# MCU_V1.net
KiCad netlist of a schematic drawn in EAGLE
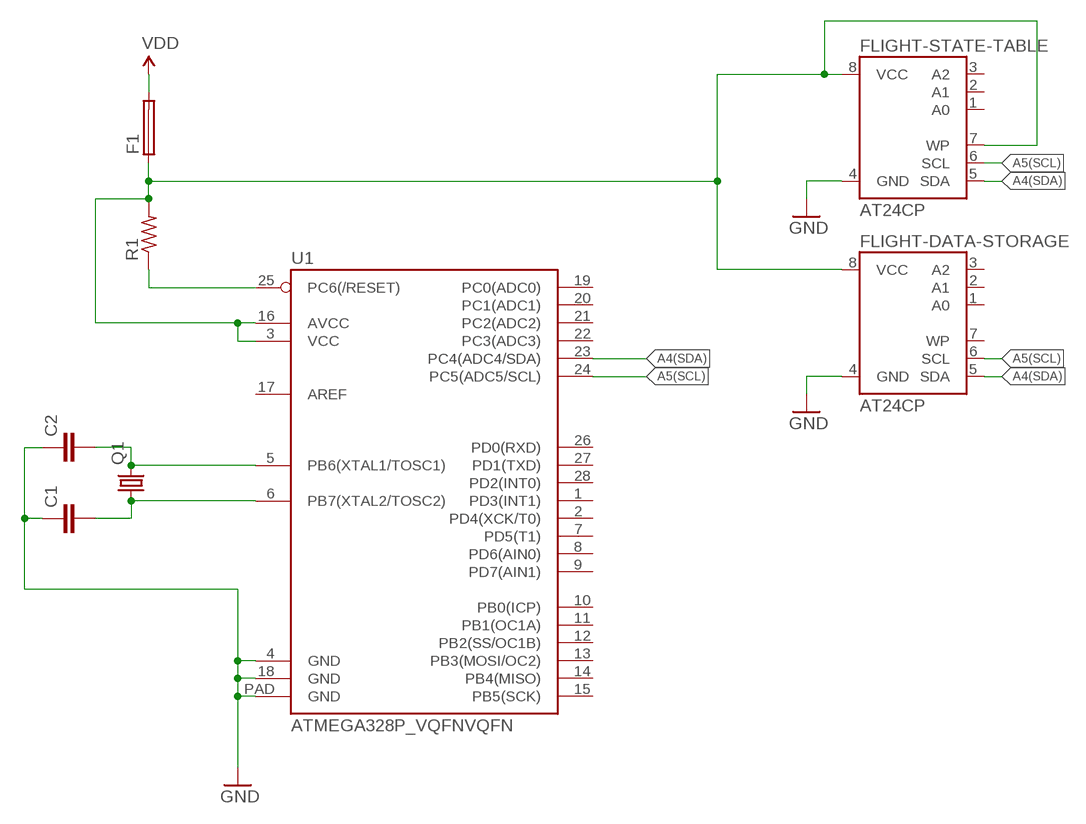
[diagram p0: schematic, sheet 1]

(export (version "E")
  (design (tool "Eeschema 10.0.6"))
  (components
    (comp (ref "C1")
      (value "C2,5-3")
      (footprint "eagle-import:C2.5-3")
      (libsource (lib "eagle-import") (part "C2,5-3"))
    )
    (comp (ref "C2")
      (value "C2,5-3")
      (footprint "eagle-import:C2.5-3")
      (libsource (lib "eagle-import") (part "C2,5-3"))
    )
    (comp (ref "F1")
      (value "19559")
      (footprint "eagle-import:19559")
      (fields (field (name "MPN") "55900000001"))
      (libsource (lib "eagle-import") (part "19559"))
    )
    (comp (ref "FLIGHT-DATA-STORAGE")
      (value "AT24CP")
      (footprint "eagle-import:DIL08")
      (fields (field (name "MPN") "AT24C1024BW-SH-B"))
      (libsource (lib "eagle-import") (part "AT24CP"))
    )
    (comp (ref "FLIGHT-STATE-TABLE")
      (value "AT24CP")
      (footprint "eagle-import:DIL08")
      (fields (field (name "MPN") "AT24C1024BW-SH-B"))
      (libsource (lib "eagle-import") (part "AT24CP"))
    )
    (comp (ref "Q1")
      (value "CRYSTALHC33U-V")
      (footprint "eagle-import:HC33U-V")
      (libsource (lib "eagle-import") (part "CRYSTALHC33U-V"))
    )
    (comp (ref "R1")
      (value "R-US_R0805")
      (footprint "eagle-import:R0805")
      (libsource (lib "eagle-import") (part "R-US_R0805"))
    )
    (comp (ref "U1")
      (value "ATMEGA328P_VQFNVQFN")
      (footprint "eagle-import:VQFN-28")
      (libsource (lib "eagle-import") (part "ATMEGA328P_VQFNVQFN"))
    )
  )
  (nets
    (net (code "1") (name "A4(SDA)") (class "Default")
      (node (ref "FLIGHT-DATA-STORAGE") (pin "5") (pinfunction "SDA_5") (pintype "bidirectional"))
      (node (ref "FLIGHT-STATE-TABLE") (pin "5") (pinfunction "SDA_5") (pintype "bidirectional"))
      (node (ref "U1") (pin "23") (pinfunction "PC4(ADC4/SDA)_23") (pintype "bidirectional"))
    )
    (net (code "2") (name "A5(SCL)") (class "Default")
      (node (ref "FLIGHT-DATA-STORAGE") (pin "6") (pinfunction "SCL_6") (pintype "bidirectional"))
      (node (ref "FLIGHT-STATE-TABLE") (pin "6") (pinfunction "SCL_6") (pintype "bidirectional"))
      (node (ref "U1") (pin "24") (pinfunction "PC5(ADC5/SCL)_24") (pintype "bidirectional"))
    )
    (net (code "3") (name "GND") (class "Default")
      (node (ref "C1") (pin "1") (pinfunction "1_1") (pintype "passive"))
      (node (ref "C2") (pin "1") (pinfunction "1_1") (pintype "passive"))
      (node (ref "FLIGHT-DATA-STORAGE") (pin "4") (pinfunction "GND_4") (pintype "power_in"))
      (node (ref "FLIGHT-STATE-TABLE") (pin "4") (pinfunction "GND_4") (pintype "power_in"))
      (node (ref "U1") (pin "18") (pinfunction "GND_18") (pintype "bidirectional"))
      (node (ref "U1") (pin "4") (pinfunction "GND_4") (pintype "bidirectional"))
      (node (ref "U1") (pin "PAD") (pinfunction "GND_PAD") (pintype "bidirectional"))
    )
    (net (code "4") (name "Net-(FLIGHT-DATA-STORAGE-VCC)") (class "Default")
      (node (ref "F1") (pin "1") (pinfunction "1_1") (pintype "passive"))
      (node (ref "FLIGHT-DATA-STORAGE") (pin "8") (pinfunction "VCC_8") (pintype "power_in"))
      (node (ref "FLIGHT-STATE-TABLE") (pin "7") (pinfunction "WP_7") (pintype "input"))
      (node (ref "FLIGHT-STATE-TABLE") (pin "8") (pinfunction "VCC_8") (pintype "power_in"))
      (node (ref "R1") (pin "2") (pinfunction "2_2") (pintype "passive"))
      (node (ref "U1") (pin "16") (pinfunction "AVCC_16") (pintype "bidirectional"))
      (node (ref "U1") (pin "3") (pinfunction "VCC_3") (pintype "bidirectional"))
    )
    (net (code "5") (name "Net-(U1-PB6(XTAL1{slash}TOSC1))") (class "Default")
      (node (ref "C2") (pin "2") (pinfunction "2_2") (pintype "passive"))
      (node (ref "Q1") (pin "2") (pinfunction "2_2") (pintype "passive"))
      (node (ref "U1") (pin "5") (pinfunction "PB6(XTAL1/TOSC1)_5") (pintype "bidirectional"))
    )
    (net (code "6") (name "Net-(U1-PB7(XTAL2{slash}TOSC2))") (class "Default")
      (node (ref "C1") (pin "2") (pinfunction "2_2") (pintype "passive"))
      (node (ref "Q1") (pin "1") (pinfunction "1_1") (pintype "passive"))
      (node (ref "U1") (pin "6") (pinfunction "PB7(XTAL2/TOSC2)_6") (pintype "bidirectional"))
    )
    (net (code "7") (name "Net-(U1-PC6({slash}RESET))") (class "Default")
      (node (ref "R1") (pin "1") (pinfunction "1_1") (pintype "passive"))
      (node (ref "U1") (pin "25") (pinfunction "PC6(/RESET)_25") (pintype "bidirectional"))
    )
    (net (code "8") (name "VDD") (class "Default")
      (node (ref "F1") (pin "2") (pinfunction "2_2") (pintype "passive"))
    )
    (net (code "9") (name "unconnected-(FLIGHT-DATA-STORAGE-A0-Pad1)") (class "Default")
      (node (ref "FLIGHT-DATA-STORAGE") (pin "1") (pinfunction "A0_1") (pintype "input"))
    )
    (net (code "10") (name "unconnected-(FLIGHT-DATA-STORAGE-A1-Pad2)") (class "Default")
      (node (ref "FLIGHT-DATA-STORAGE") (pin "2") (pinfunction "A1_2") (pintype "input"))
    )
    (net (code "11") (name "unconnected-(FLIGHT-DATA-STORAGE-A2-Pad3)") (class "Default")
      (node (ref "FLIGHT-DATA-STORAGE") (pin "3") (pinfunction "A2_3") (pintype "input"))
    )
    (net (code "12") (name "unconnected-(FLIGHT-DATA-STORAGE-WP-Pad7)") (class "Default")
      (node (ref "FLIGHT-DATA-STORAGE") (pin "7") (pinfunction "WP_7") (pintype "input"))
    )
    (net (code "13") (name "unconnected-(FLIGHT-STATE-TABLE-A0-Pad1)") (class "Default")
      (node (ref "FLIGHT-STATE-TABLE") (pin "1") (pinfunction "A0_1") (pintype "input"))
    )
    (net (code "14") (name "unconnected-(FLIGHT-STATE-TABLE-A1-Pad2)") (class "Default")
      (node (ref "FLIGHT-STATE-TABLE") (pin "2") (pinfunction "A1_2") (pintype "input"))
    )
    (net (code "15") (name "unconnected-(FLIGHT-STATE-TABLE-A2-Pad3)") (class "Default")
      (node (ref "FLIGHT-STATE-TABLE") (pin "3") (pinfunction "A2_3") (pintype "input"))
    )
    (net (code "16") (name "unconnected-(U1-AREF-Pad17)") (class "Default")
      (node (ref "U1") (pin "17") (pinfunction "AREF_17") (pintype "bidirectional"))
    )
    (net (code "17") (name "unconnected-(U1-PB0(ICP)-Pad10)") (class "Default")
      (node (ref "U1") (pin "10") (pinfunction "PB0(ICP)_10") (pintype "bidirectional"))
    )
    (net (code "18") (name "unconnected-(U1-PB1(OC1A)-Pad11)") (class "Default")
      (node (ref "U1") (pin "11") (pinfunction "PB1(OC1A)_11") (pintype "bidirectional"))
    )
    (net (code "19") (name "unconnected-(U1-PB2(SS{slash}OC1B)-Pad12)") (class "Default")
      (node (ref "U1") (pin "12") (pinfunction "PB2(SS/OC1B)_12") (pintype "bidirectional"))
    )
    (net (code "20") (name "unconnected-(U1-PB3(MOSI{slash}OC2)-Pad13)") (class "Default")
      (node (ref "U1") (pin "13") (pinfunction "PB3(MOSI/OC2)_13") (pintype "bidirectional"))
    )
    (net (code "21") (name "unconnected-(U1-PB4(MISO)-Pad14)") (class "Default")
      (node (ref "U1") (pin "14") (pinfunction "PB4(MISO)_14") (pintype "bidirectional"))
    )
    (net (code "22") (name "unconnected-(U1-PB5(SCK)-Pad15)") (class "Default")
      (node (ref "U1") (pin "15") (pinfunction "PB5(SCK)_15") (pintype "bidirectional"))
    )
    (net (code "23") (name "unconnected-(U1-PC0(ADC0)-Pad19)") (class "Default")
      (node (ref "U1") (pin "19") (pinfunction "PC0(ADC0)_19") (pintype "bidirectional"))
    )
    (net (code "24") (name "unconnected-(U1-PC1(ADC1)-Pad20)") (class "Default")
      (node (ref "U1") (pin "20") (pinfunction "PC1(ADC1)_20") (pintype "bidirectional"))
    )
    (net (code "25") (name "unconnected-(U1-PC2(ADC2)-Pad21)") (class "Default")
      (node (ref "U1") (pin "21") (pinfunction "PC2(ADC2)_21") (pintype "bidirectional"))
    )
    (net (code "26") (name "unconnected-(U1-PC3(ADC3)-Pad22)") (class "Default")
      (node (ref "U1") (pin "22") (pinfunction "PC3(ADC3)_22") (pintype "bidirectional"))
    )
    (net (code "27") (name "unconnected-(U1-PD0(RXD)-Pad26)") (class "Default")
      (node (ref "U1") (pin "26") (pinfunction "PD0(RXD)_26") (pintype "bidirectional"))
    )
    (net (code "28") (name "unconnected-(U1-PD1(TXD)-Pad27)") (class "Default")
      (node (ref "U1") (pin "27") (pinfunction "PD1(TXD)_27") (pintype "bidirectional"))
    )
    (net (code "29") (name "unconnected-(U1-PD2(INT0)-Pad28)") (class "Default")
      (node (ref "U1") (pin "28") (pinfunction "PD2(INT0)_28") (pintype "bidirectional"))
    )
    (net (code "30") (name "unconnected-(U1-PD3(INT1)-Pad1)") (class "Default")
      (node (ref "U1") (pin "1") (pinfunction "PD3(INT1)_1") (pintype "bidirectional"))
    )
    (net (code "31") (name "unconnected-(U1-PD4(XCK{slash}T0)-Pad2)") (class "Default")
      (node (ref "U1") (pin "2") (pinfunction "PD4(XCK/T0)_2") (pintype "bidirectional"))
    )
    (net (code "32") (name "unconnected-(U1-PD5(T1)-Pad7)") (class "Default")
      (node (ref "U1") (pin "7") (pinfunction "PD5(T1)_7") (pintype "bidirectional"))
    )
    (net (code "33") (name "unconnected-(U1-PD6(AIN0)-Pad8)") (class "Default")
      (node (ref "U1") (pin "8") (pinfunction "PD6(AIN0)_8") (pintype "bidirectional"))
    )
    (net (code "34") (name "unconnected-(U1-PD7(AIN1)-Pad9)") (class "Default")
      (node (ref "U1") (pin "9") (pinfunction "PD7(AIN1)_9") (pintype "bidirectional"))
    )
  )
)
